# hri_hand_v2.net
KiCad netlist of a schematic drawn in Altium Designer
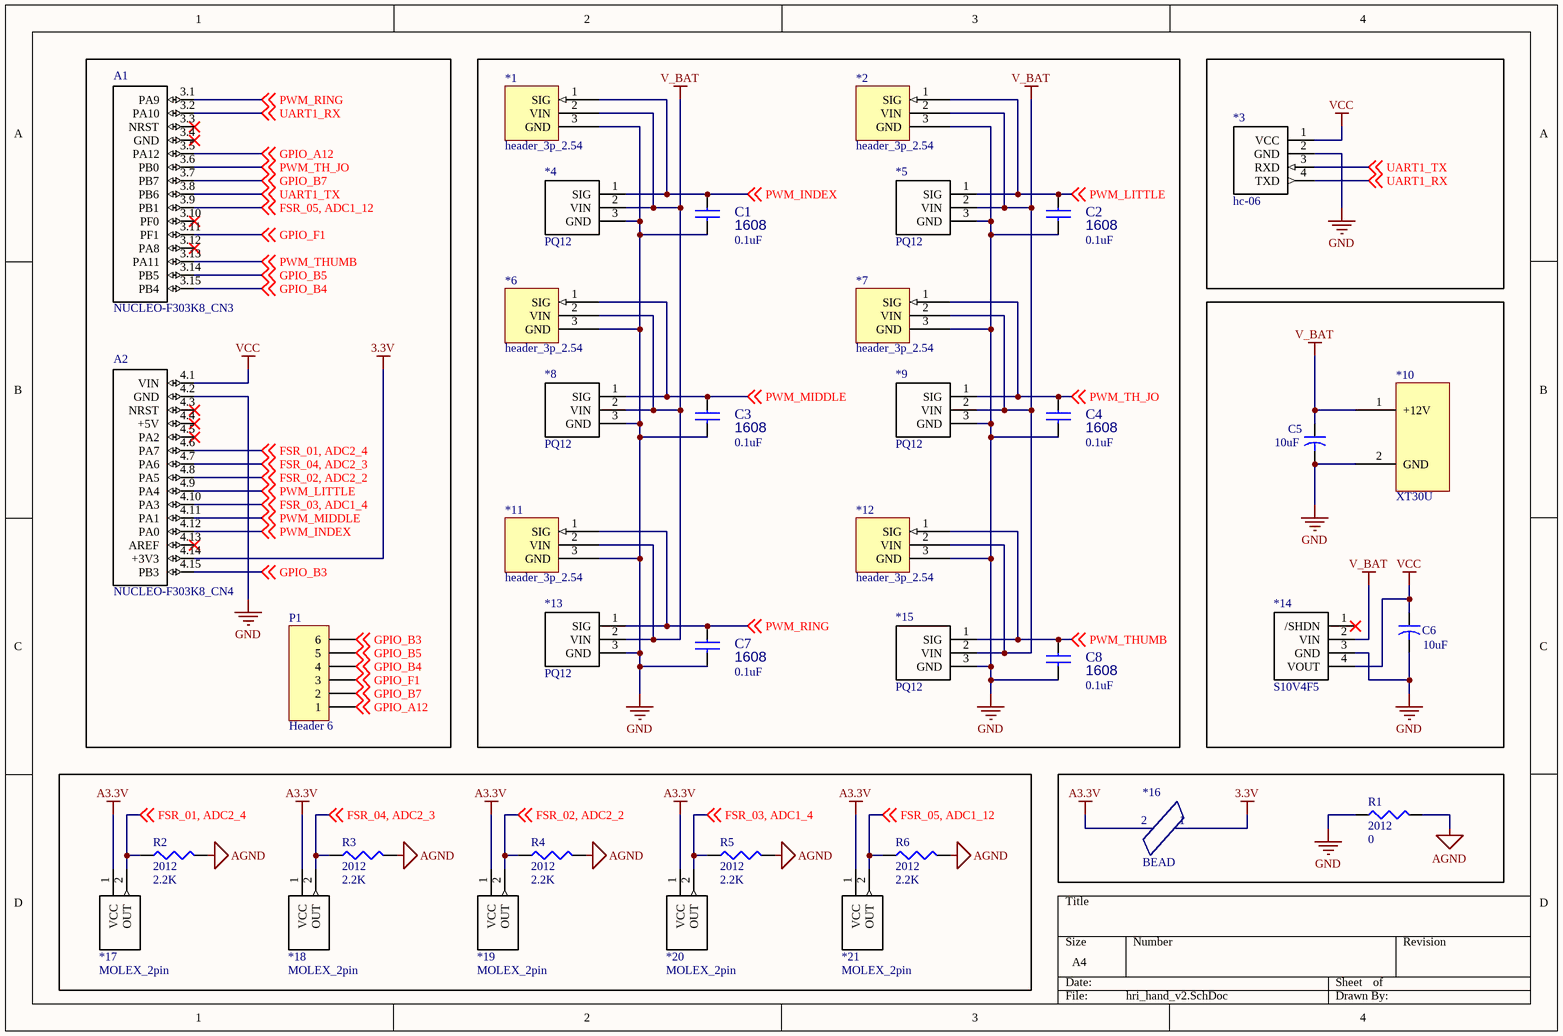
[diagram p0: hri_hand_v2.SchDoc]

(export (version "E")
  (design (tool "Eeschema 10.0.6"))
  (components
    (comp (ref "*1")
      (value "header_3p_2.54")
      (footprint "header_3x1_2.54")
      (libsource (lib "hri_hand") (part "header_3p_2.54"))
    )
    (comp (ref "*2")
      (value "header_3p_2.54")
      (footprint "header_3x1_2.54")
      (libsource (lib "hri_hand") (part "header_3p_2.54"))
    )
    (comp (ref "*3")
      (value "hc-06")
      (footprint "header_4x1_2.54")
      (libsource (lib "hri_hand") (part "hc-06"))
    )
    (comp (ref "*4") (value "PQ12") (footprint "molex_3p_2.54") (libsource (lib "hri_hand") (part "PQ12")))
    (comp (ref "*5") (value "PQ12") (footprint "molex_3p_2.54") (libsource (lib "hri_hand") (part "PQ12")))
    (comp (ref "*6")
      (value "header_3p_2.54")
      (footprint "header_3x1_2.54")
      (libsource (lib "hri_hand") (part "header_3p_2.54"))
    )
    (comp (ref "*7")
      (value "header_3p_2.54")
      (footprint "header_3x1_2.54")
      (libsource (lib "hri_hand") (part "header_3p_2.54"))
    )
    (comp (ref "*8") (value "PQ12") (footprint "molex_3p_2.54") (libsource (lib "hri_hand") (part "PQ12")))
    (comp (ref "*9") (value "PQ12") (footprint "molex_3p_2.54") (libsource (lib "hri_hand") (part "PQ12")))
    (comp (ref "*10") (value "XT30U") (footprint "XT30F") (libsource (lib "hri_hand") (part "XT30U")))
    (comp (ref "*11")
      (value "header_3p_2.54")
      (footprint "header_3x1_2.54")
      (libsource (lib "hri_hand") (part "header_3p_2.54"))
    )
    (comp (ref "*12")
      (value "header_3p_2.54")
      (footprint "header_3x1_2.54")
      (libsource (lib "hri_hand") (part "header_3p_2.54"))
    )
    (comp (ref "*13") (value "PQ12") (footprint "molex_3p_2.54") (libsource (lib "hri_hand") (part "PQ12")))
    (comp (ref "*14")
      (value "S10V4F5")
      (footprint "header_4x1_2.54")
      (libsource (lib "hri_hand") (part "S10V4F5"))
    )
    (comp (ref "*15") (value "PQ12") (footprint "molex_3p_2.54") (libsource (lib "hri_hand") (part "PQ12")))
    (comp (ref "*16") (value "BEAD") (footprint "L-1608-SS") (libsource (lib "hri_hand") (part "BEAD")))
    (comp (ref "*17")
      (value "MOLEX_2pin")
      (footprint "molex_2p_2.54")
      (libsource (lib "hri_hand") (part "MOLEX_2pin"))
    )
    (comp (ref "*18")
      (value "MOLEX_2pin")
      (footprint "molex_2p_2.54")
      (libsource (lib "hri_hand") (part "MOLEX_2pin"))
    )
    (comp (ref "*19")
      (value "MOLEX_2pin")
      (footprint "molex_2p_2.54")
      (libsource (lib "hri_hand") (part "MOLEX_2pin"))
    )
    (comp (ref "*20")
      (value "MOLEX_2pin")
      (footprint "molex_2p_2.54")
      (libsource (lib "hri_hand") (part "MOLEX_2pin"))
    )
    (comp (ref "*21")
      (value "MOLEX_2pin")
      (footprint "molex_2p_2.54")
      (libsource (lib "hri_hand") (part "MOLEX_2pin"))
    )
    (comp (ref "A1")
      (value "NUCLEO-F303K8_CN3")
      (footprint "header_1*15_3")
      (description "STM32 Nucleo-32 development board with STM32F303K8T6 MCU, supports Arduino connectivity")
      (fields (field (name "MP") "NUCLEO-F303K8") (field (name "MF") "STMicroelectronics"))
      (libsource (lib "hri_hand") (part "NUCLEO-F303K8_CN3"))
    )
    (comp (ref "A2")
      (value "NUCLEO-F303K8_CN4")
      (footprint "header_1*15_4")
      (description "STM32 Nucleo-32 development board with STM32F303K8T6 MCU, supports Arduino connectivity")
      (fields (field (name "MP") "NUCLEO-F303K8") (field (name "MF") "STMicroelectronics"))
      (libsource (lib "hri_hand") (part "NUCLEO-F303K8_CN4"))
    )
    (comp (ref "C1")
      (value "1608")
      (footprint "CAP-1608-SS")
      (fields (field (name "ALTIUM_VALUE") "0.1uF"))
      (libsource (lib "*") (part "CAP NP"))
    )
    (comp (ref "C2")
      (value "1608")
      (footprint "CAP-1608-SS")
      (fields (field (name "ALTIUM_VALUE") "0.1uF"))
      (libsource (lib "*") (part "CAP NP"))
    )
    (comp (ref "C3")
      (value "1608")
      (footprint "CAP-1608-SS")
      (fields (field (name "ALTIUM_VALUE") "0.1uF"))
      (libsource (lib "*") (part "CAP NP"))
    )
    (comp (ref "C4")
      (value "1608")
      (footprint "CAP-1608-SS")
      (fields (field (name "ALTIUM_VALUE") "0.1uF"))
      (libsource (lib "*") (part "CAP NP"))
    )
    (comp (ref "C5")
      (value "10uF")
      (footprint "C-10UF/16V")
      (description "Capacitor")
      (fields (field (name "PUBLISHER") "Altium Limited"))
      (libsource (lib "Miscellaneous Devices") (part "Cap2"))
    )
    (comp (ref "C6")
      (value "10uF")
      (footprint "C-10UF/16V")
      (description "Capacitor")
      (fields (field (name "PUBLISHER") "Altium Limited"))
      (libsource (lib "Miscellaneous Devices") (part "Cap2"))
    )
    (comp (ref "C7")
      (value "1608")
      (footprint "CAP-1608-SS")
      (fields (field (name "ALTIUM_VALUE") "0.1uF"))
      (libsource (lib "*") (part "CAP NP"))
    )
    (comp (ref "C8")
      (value "1608")
      (footprint "CAP-1608-SS")
      (fields (field (name "ALTIUM_VALUE") "0.1uF"))
      (libsource (lib "*") (part "CAP NP"))
    )
    (comp (ref "P1")
      (value "Header 6")
      (footprint "HDR1X6")
      (description "Header, 6-Pin")
      (fields (field (name "PUBLISHER") "Altium Limited"))
      (libsource (lib "Miscellaneous Connectors") (part "Header 6"))
    )
    (comp (ref "R1")
      (value "2012")
      (footprint "RES-2012")
      (description "Resistor")
      (fields (field (name "ALTIUM_VALUE") "0") (field (name "PUBLISHER") "Altium Limited"))
      (libsource (lib "Miscellaneous Devices") (part "Res3"))
    )
    (comp (ref "R2")
      (value "2012")
      (footprint "hri_hand:RES-2012")
      (description "Resistor")
      (fields (field (name "ALTIUM_VALUE") "2.2K") (field (name "PUBLISHER") "Altium Limited"))
      (libsource (lib "Miscellaneous Devices") (part "Res3"))
    )
    (comp (ref "R3")
      (value "2012")
      (footprint "RES-2012")
      (description "Resistor")
      (fields (field (name "ALTIUM_VALUE") "2.2K") (field (name "PUBLISHER") "Altium Limited"))
      (libsource (lib "Miscellaneous Devices") (part "Res3"))
    )
    (comp (ref "R4")
      (value "2012")
      (footprint "RES-2012")
      (description "Resistor")
      (fields (field (name "ALTIUM_VALUE") "2.2K") (field (name "PUBLISHER") "Altium Limited"))
      (libsource (lib "Miscellaneous Devices") (part "Res3"))
    )
    (comp (ref "R5")
      (value "2012")
      (footprint "RES-2012")
      (description "Resistor")
      (fields (field (name "ALTIUM_VALUE") "2.2K") (field (name "PUBLISHER") "Altium Limited"))
      (libsource (lib "Miscellaneous Devices") (part "Res3"))
    )
    (comp (ref "R6")
      (value "2012")
      (footprint "RES-2012")
      (description "Resistor")
      (fields (field (name "ALTIUM_VALUE") "2.2K") (field (name "PUBLISHER") "Altium Limited"))
      (libsource (lib "Miscellaneous Devices") (part "Res3"))
    )
  )
  (nets
    (net (code "1") (name "3.3V") (class "Default")
      (node (ref "*16") (pin "1") (pinfunction "1_1") (pintype "passive"))
      (node (ref "A2") (pin "4.14") (pinfunction "+3V3_4.14") (pintype "bidirectional"))
    )
    (net (code "2") (name "A3.3V") (class "Default")
      (node (ref "*16") (pin "2") (pinfunction "2_2") (pintype "passive"))
      (node (ref "*17") (pin "1") (pinfunction "VCC_1") (pintype "power_in"))
      (node (ref "*18") (pin "1") (pinfunction "VCC_1") (pintype "power_in"))
      (node (ref "*19") (pin "1") (pinfunction "VCC_1") (pintype "power_in"))
      (node (ref "*20") (pin "1") (pinfunction "VCC_1") (pintype "power_in"))
      (node (ref "*21") (pin "1") (pinfunction "VCC_1") (pintype "power_in"))
    )
    (net (code "3") (name "AGND") (class "Default")
      (node (ref "R1") (pin "2") (pinfunction "2_2") (pintype "passive"))
      (node (ref "R2") (pin "2") (pinfunction "2_2") (pintype "passive"))
      (node (ref "R3") (pin "2") (pinfunction "2_2") (pintype "passive"))
      (node (ref "R4") (pin "2") (pinfunction "2_2") (pintype "passive"))
      (node (ref "R5") (pin "2") (pinfunction "2_2") (pintype "passive"))
      (node (ref "R6") (pin "2") (pinfunction "2_2") (pintype "passive"))
    )
    (net (code "4") (name "FSR_01, ADC2_4") (class "Default")
      (node (ref "*17") (pin "2") (pinfunction "OUT_2") (pintype "output"))
      (node (ref "A2") (pin "4.6") (pinfunction "PA7_4.6") (pintype "bidirectional"))
      (node (ref "R2") (pin "1") (pinfunction "1_1") (pintype "passive"))
    )
    (net (code "5") (name "FSR_02, ADC2_2") (class "Default")
      (node (ref "*19") (pin "2") (pinfunction "OUT_2") (pintype "output"))
      (node (ref "A2") (pin "4.8") (pinfunction "PA5_4.8") (pintype "bidirectional"))
      (node (ref "R4") (pin "1") (pinfunction "1_1") (pintype "passive"))
    )
    (net (code "6") (name "FSR_03, ADC1_4") (class "Default")
      (node (ref "*20") (pin "2") (pinfunction "OUT_2") (pintype "output"))
      (node (ref "A2") (pin "4.10") (pinfunction "PA3_4.10") (pintype "bidirectional"))
      (node (ref "R5") (pin "1") (pinfunction "1_1") (pintype "passive"))
    )
    (net (code "7") (name "FSR_04, ADC2_3") (class "Default")
      (node (ref "*18") (pin "2") (pinfunction "OUT_2") (pintype "output"))
      (node (ref "A2") (pin "4.7") (pinfunction "PA6_4.7") (pintype "bidirectional"))
      (node (ref "R3") (pin "1") (pinfunction "1_1") (pintype "passive"))
    )
    (net (code "8") (name "FSR_05, ADC1_12") (class "Default")
      (node (ref "*21") (pin "2") (pinfunction "OUT_2") (pintype "output"))
      (node (ref "A1") (pin "3.9") (pinfunction "PB1_3.9") (pintype "bidirectional"))
      (node (ref "R6") (pin "1") (pinfunction "1_1") (pintype "passive"))
    )
    (net (code "9") (name "GND") (class "Default")
      (node (ref "*1") (pin "3") (pinfunction "GND_3") (pintype "power_in"))
      (node (ref "*10") (pin "2") (pinfunction "GND_2") (pintype "power_in"))
      (node (ref "*11") (pin "3") (pinfunction "GND_3") (pintype "power_in"))
      (node (ref "*12") (pin "3") (pinfunction "GND_3") (pintype "power_in"))
      (node (ref "*13") (pin "3") (pinfunction "GND_3") (pintype "power_in"))
      (node (ref "*14") (pin "3") (pinfunction "GND_3") (pintype "power_in"))
      (node (ref "*15") (pin "3") (pinfunction "GND_3") (pintype "power_in"))
      (node (ref "*2") (pin "3") (pinfunction "GND_3") (pintype "power_in"))
      (node (ref "*3") (pin "2") (pinfunction "GND_2") (pintype "power_in"))
      (node (ref "*4") (pin "3") (pinfunction "GND_3") (pintype "power_in"))
      (node (ref "*5") (pin "3") (pinfunction "GND_3") (pintype "power_in"))
      (node (ref "*6") (pin "3") (pinfunction "GND_3") (pintype "power_in"))
      (node (ref "*7") (pin "3") (pinfunction "GND_3") (pintype "power_in"))
      (node (ref "*8") (pin "3") (pinfunction "GND_3") (pintype "power_in"))
      (node (ref "*9") (pin "3") (pinfunction "GND_3") (pintype "power_in"))
      (node (ref "A2") (pin "4.2") (pinfunction "GND_4.2") (pintype "bidirectional"))
      (node (ref "C1") (pin "2") (pinfunction "2_2") (pintype "passive"))
      (node (ref "C2") (pin "2") (pinfunction "2_2") (pintype "passive"))
      (node (ref "C3") (pin "2") (pinfunction "2_2") (pintype "passive"))
      (node (ref "C4") (pin "2") (pinfunction "2_2") (pintype "passive"))
      (node (ref "C5") (pin "2") (pinfunction "2_2") (pintype "passive"))
      (node (ref "C6") (pin "2") (pinfunction "2_2") (pintype "passive"))
      (node (ref "C7") (pin "2") (pinfunction "2_2") (pintype "passive"))
      (node (ref "C8") (pin "2") (pinfunction "2_2") (pintype "passive"))
      (node (ref "R1") (pin "1") (pinfunction "1_1") (pintype "passive"))
    )
    (net (code "10") (name "GPIO_A12") (class "Default")
      (node (ref "A1") (pin "3.5") (pinfunction "PA12_3.5") (pintype "bidirectional"))
      (node (ref "P1") (pin "1") (pinfunction "1_1") (pintype "passive"))
    )
    (net (code "11") (name "GPIO_B3") (class "Default")
      (node (ref "A2") (pin "4.15") (pinfunction "PB3_4.15") (pintype "bidirectional"))
      (node (ref "P1") (pin "6") (pinfunction "6_6") (pintype "passive"))
    )
    (net (code "12") (name "GPIO_B4") (class "Default")
      (node (ref "A1") (pin "3.15") (pinfunction "PB4_3.15") (pintype "bidirectional"))
      (node (ref "P1") (pin "4") (pinfunction "4_4") (pintype "passive"))
    )
    (net (code "13") (name "GPIO_B5") (class "Default")
      (node (ref "A1") (pin "3.14") (pinfunction "PB5_3.14") (pintype "bidirectional"))
      (node (ref "P1") (pin "5") (pinfunction "5_5") (pintype "passive"))
    )
    (net (code "14") (name "GPIO_B7") (class "Default")
      (node (ref "A1") (pin "3.7") (pinfunction "PB7_3.7") (pintype "bidirectional"))
      (node (ref "P1") (pin "2") (pinfunction "2_2") (pintype "passive"))
    )
    (net (code "15") (name "GPIO_F1") (class "Default")
      (node (ref "A1") (pin "3.11") (pinfunction "PF1_3.11") (pintype "bidirectional"))
      (node (ref "P1") (pin "3") (pinfunction "3_3") (pintype "passive"))
    )
    (net (code "16") (name "PWM_INDEX") (class "Default")
      (node (ref "*1") (pin "1") (pinfunction "SIG_1") (pintype "input"))
      (node (ref "*4") (pin "1") (pinfunction "SIG_1") (pintype "power_in"))
      (node (ref "A2") (pin "4.12") (pinfunction "PA0_4.12") (pintype "bidirectional"))
      (node (ref "C1") (pin "1") (pinfunction "1_1") (pintype "passive"))
    )
    (net (code "17") (name "PWM_LITTLE") (class "Default")
      (node (ref "*2") (pin "1") (pinfunction "SIG_1") (pintype "input"))
      (node (ref "*5") (pin "1") (pinfunction "SIG_1") (pintype "power_in"))
      (node (ref "A2") (pin "4.9") (pinfunction "PA4_4.9") (pintype "bidirectional"))
      (node (ref "C2") (pin "1") (pinfunction "1_1") (pintype "passive"))
    )
    (net (code "18") (name "PWM_MIDDLE") (class "Default")
      (node (ref "*6") (pin "1") (pinfunction "SIG_1") (pintype "input"))
      (node (ref "*8") (pin "1") (pinfunction "SIG_1") (pintype "power_in"))
      (node (ref "A2") (pin "4.11") (pinfunction "PA1_4.11") (pintype "bidirectional"))
      (node (ref "C3") (pin "1") (pinfunction "1_1") (pintype "passive"))
    )
    (net (code "19") (name "PWM_RING") (class "Default")
      (node (ref "*11") (pin "1") (pinfunction "SIG_1") (pintype "input"))
      (node (ref "*13") (pin "1") (pinfunction "SIG_1") (pintype "power_in"))
      (node (ref "A1") (pin "3.1") (pinfunction "PA9_3.1") (pintype "bidirectional"))
      (node (ref "C7") (pin "1") (pinfunction "1_1") (pintype "passive"))
    )
    (net (code "20") (name "PWM_THUMB") (class "Default")
      (node (ref "*12") (pin "1") (pinfunction "SIG_1") (pintype "input"))
      (node (ref "*15") (pin "1") (pinfunction "SIG_1") (pintype "power_in"))
      (node (ref "A1") (pin "3.13") (pinfunction "PA11_3.13") (pintype "bidirectional"))
      (node (ref "C8") (pin "1") (pinfunction "1_1") (pintype "passive"))
    )
    (net (code "21") (name "PWM_TH_JO") (class "Default")
      (node (ref "*7") (pin "1") (pinfunction "SIG_1") (pintype "input"))
      (node (ref "*9") (pin "1") (pinfunction "SIG_1") (pintype "power_in"))
      (node (ref "A1") (pin "3.6") (pinfunction "PB0_3.6") (pintype "bidirectional"))
      (node (ref "C4") (pin "1") (pinfunction "1_1") (pintype "passive"))
    )
    (net (code "22") (name "UART1_RX") (class "Default")
      (node (ref "*3") (pin "4") (pinfunction "TXD_4") (pintype "output"))
      (node (ref "A1") (pin "3.2") (pinfunction "PA10_3.2") (pintype "bidirectional"))
    )
    (net (code "23") (name "UART1_TX") (class "Default")
      (node (ref "*3") (pin "3") (pinfunction "RXD_3") (pintype "input"))
      (node (ref "A1") (pin "3.8") (pinfunction "PB6_3.8") (pintype "bidirectional"))
    )
    (net (code "24") (name "VCC") (class "Default")
      (node (ref "*14") (pin "4") (pinfunction "VOUT_4") (pintype "power_in"))
      (node (ref "*3") (pin "1") (pinfunction "VCC_1") (pintype "power_in"))
      (node (ref "A2") (pin "4.1") (pinfunction "VIN_4.1") (pintype "bidirectional"))
      (node (ref "C6") (pin "1") (pinfunction "1_1") (pintype "passive"))
    )
    (net (code "25") (name "V_BAT") (class "Default")
      (node (ref "*1") (pin "2") (pinfunction "VIN_2") (pintype "power_in"))
      (node (ref "*10") (pin "1") (pinfunction "+12V_1") (pintype "power_in"))
      (node (ref "*11") (pin "2") (pinfunction "VIN_2") (pintype "power_in"))
      (node (ref "*12") (pin "2") (pinfunction "VIN_2") (pintype "power_in"))
      (node (ref "*13") (pin "2") (pinfunction "VIN_2") (pintype "power_in"))
      (node (ref "*14") (pin "2") (pinfunction "VIN_2") (pintype "power_in"))
      (node (ref "*15") (pin "2") (pinfunction "VIN_2") (pintype "power_in"))
      (node (ref "*2") (pin "2") (pinfunction "VIN_2") (pintype "power_in"))
      (node (ref "*4") (pin "2") (pinfunction "VIN_2") (pintype "power_in"))
      (node (ref "*5") (pin "2") (pinfunction "VIN_2") (pintype "power_in"))
      (node (ref "*6") (pin "2") (pinfunction "VIN_2") (pintype "power_in"))
      (node (ref "*7") (pin "2") (pinfunction "VIN_2") (pintype "power_in"))
      (node (ref "*8") (pin "2") (pinfunction "VIN_2") (pintype "power_in"))
      (node (ref "*9") (pin "2") (pinfunction "VIN_2") (pintype "power_in"))
      (node (ref "C5") (pin "1") (pinfunction "1_1") (pintype "passive"))
    )
    (net (code "26") (name "unconnected-(*14-{slash}SHDN-Pad1)") (class "Default")
      (node (ref "*14") (pin "1") (pinfunction "/SHDN_1") (pintype "power_in+no_connect"))
    )
    (net (code "27") (name "unconnected-(A1-GND-Pad3.4)") (class "Default")
      (node (ref "A1") (pin "3.4") (pinfunction "GND_3.4") (pintype "bidirectional+no_connect"))
    )
    (net (code "28") (name "unconnected-(A1-NRST-Pad3.3)") (class "Default")
      (node (ref "A1") (pin "3.3") (pinfunction "NRST_3.3") (pintype "bidirectional+no_connect"))
    )
    (net (code "29") (name "unconnected-(A1-PA8-Pad3.12)") (class "Default")
      (node (ref "A1") (pin "3.12") (pinfunction "PA8_3.12") (pintype "bidirectional+no_connect"))
    )
    (net (code "30") (name "unconnected-(A1-PF0-Pad3.10)") (class "Default")
      (node (ref "A1") (pin "3.10") (pinfunction "PF0_3.10") (pintype "bidirectional+no_connect"))
    )
    (net (code "31") (name "unconnected-(A2-+5V-Pad4.4)") (class "Default")
      (node (ref "A2") (pin "4.4") (pinfunction "+5V_4.4") (pintype "bidirectional+no_connect"))
    )
    (net (code "32") (name "unconnected-(A2-AREF-Pad4.13)") (class "Default")
      (node (ref "A2") (pin "4.13") (pinfunction "AREF_4.13") (pintype "bidirectional+no_connect"))
    )
    (net (code "33") (name "unconnected-(A2-NRST-Pad4.3)") (class "Default")
      (node (ref "A2") (pin "4.3") (pinfunction "NRST_4.3") (pintype "bidirectional+no_connect"))
    )
    (net (code "34") (name "unconnected-(A2-PA2-Pad4.5)") (class "Default")
      (node (ref "A2") (pin "4.5") (pinfunction "PA2_4.5") (pintype "bidirectional+no_connect"))
    )
  )
)
